# Sensor_Power_Supply.net
KiCad netlist of a schematic drawn in Altium Designer
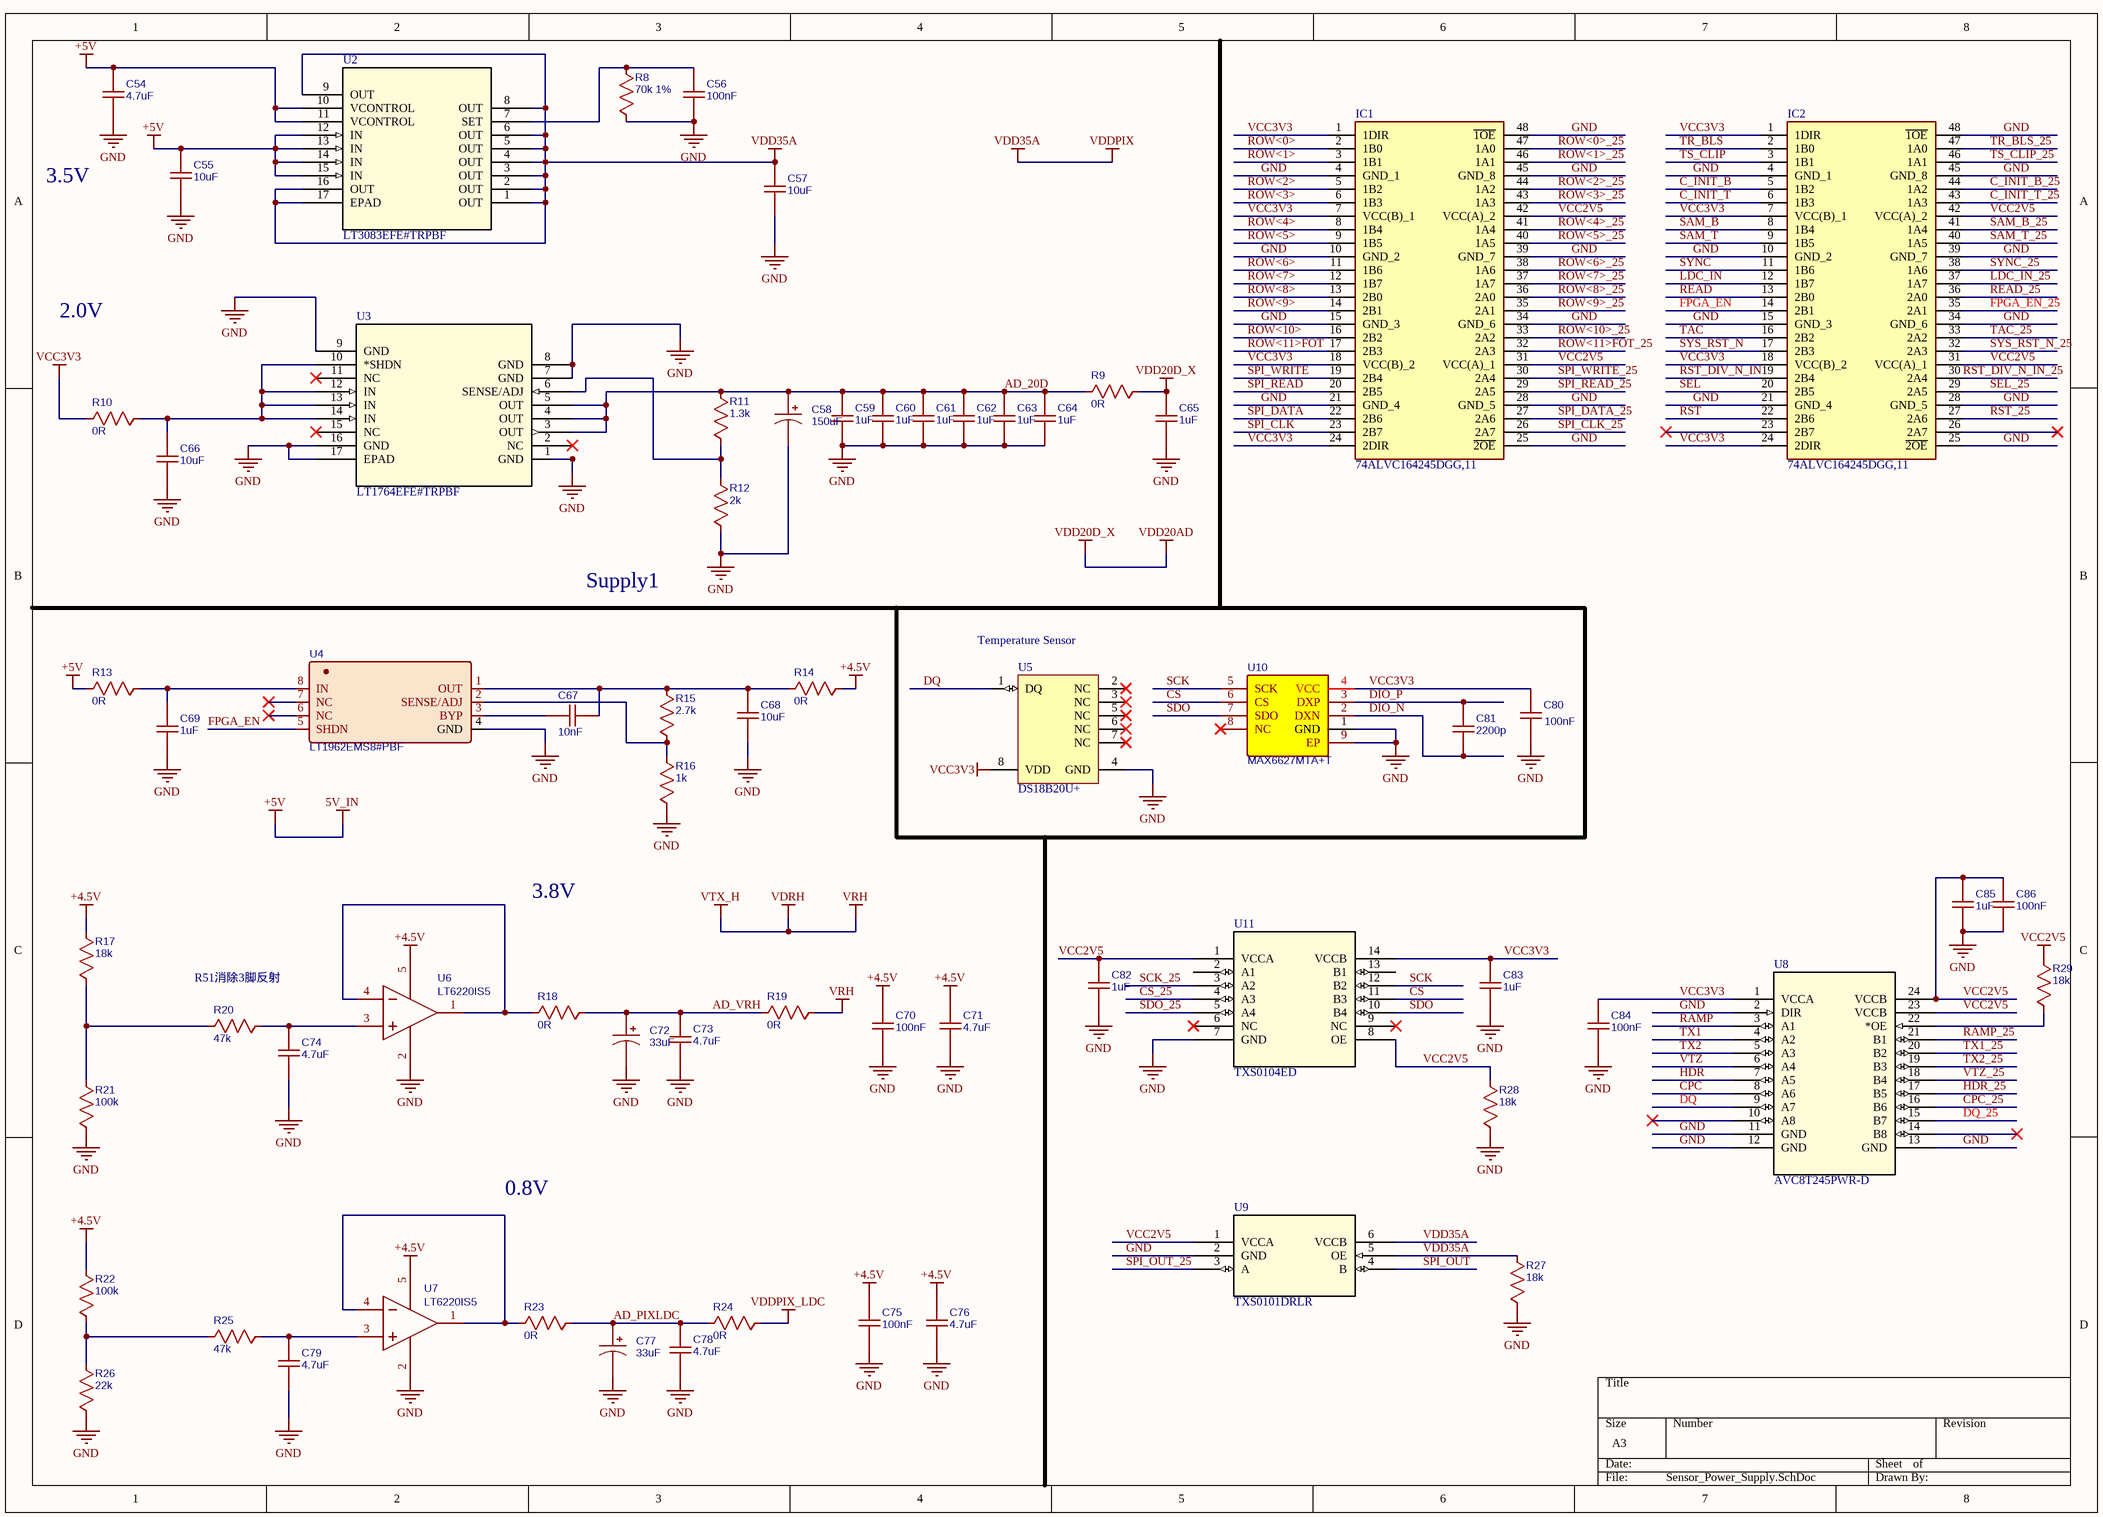
[diagram p0: Sensor_Power_Supply.SchDoc]

(export (version "E")
  (design (tool "Eeschema 10.0.6"))
  (components
    (comp (ref "C54")
      (value "4.7uF")
      (footprint "C0603")
      (fields (field (name "CONTRIBUTOR") "LCEDA_Lib"))
      (libsource (lib "Sub-board") (part "10u"))
    )
    (comp (ref "C55")
      (value "10uF")
      (footprint "C0603")
      (fields (field (name "CONTRIBUTOR") "LCEDA_Lib"))
      (libsource (lib "Sub-board") (part "10u"))
    )
    (comp (ref "C56")
      (value "100nF")
      (footprint "C0603")
      (fields (field (name "CONTRIBUTOR") "LCEDA_Lib"))
      (libsource (lib "Sub-board") (part "10u"))
    )
    (comp (ref "C57")
      (value "10uF")
      (footprint "CAP0402")
      (fields (field (name "CONTRIBUTOR") "LCEDA_Lib"))
      (libsource (lib "Sub-board") (part "10u"))
    )
    (comp (ref "C58")
      (value "150uF")
      (footprint "CASE-A_3216")
      (fields (field (name "CONTRIBUTOR") "LCEDA_Lib"))
      (libsource (lib "Sub-board") (part "150u"))
    )
    (comp (ref "C59")
      (value "1uF")
      (footprint "C0603")
      (fields (field (name "CONTRIBUTOR") "LCEDA_Lib"))
      (libsource (lib "Sub-board") (part "1u"))
    )
    (comp (ref "C60")
      (value "1uF")
      (footprint "C0603")
      (fields (field (name "CONTRIBUTOR") "LCEDA_Lib"))
      (libsource (lib "Sub-board") (part "1u"))
    )
    (comp (ref "C61")
      (value "1uF")
      (footprint "C0603")
      (fields (field (name "CONTRIBUTOR") "LCEDA_Lib"))
      (libsource (lib "Sub-board") (part "1u"))
    )
    (comp (ref "C62")
      (value "1uF")
      (footprint "C0603")
      (fields (field (name "CONTRIBUTOR") "LCEDA_Lib"))
      (libsource (lib "Sub-board") (part "1u"))
    )
    (comp (ref "C63")
      (value "1uF")
      (footprint "C0603")
      (fields (field (name "CONTRIBUTOR") "LCEDA_Lib"))
      (libsource (lib "Sub-board") (part "1u"))
    )
    (comp (ref "C64")
      (value "1uF")
      (footprint "C0603")
      (fields (field (name "CONTRIBUTOR") "LCEDA_Lib"))
      (libsource (lib "Sub-board") (part "1u"))
    )
    (comp (ref "C65")
      (value "1uF")
      (footprint "C0603")
      (fields (field (name "CONTRIBUTOR") "LCEDA_Lib"))
      (libsource (lib "Sub-board") (part "1u"))
    )
    (comp (ref "C66")
      (value "10uF")
      (footprint "C0603")
      (fields (field (name "CONTRIBUTOR") "LCEDA_Lib"))
      (libsource (lib "Sub-board") (part "10u"))
    )
    (comp (ref "C67")
      (value "10nF")
      (footprint "CAP0402")
      (fields (field (name "CONTRIBUTOR") "LCEDA_Lib"))
      (libsource (lib "Sub-board") (part "10n"))
    )
    (comp (ref "C68")
      (value "10uF")
      (footprint "C0603")
      (fields (field (name "CONTRIBUTOR") "LCEDA_Lib"))
      (libsource (lib "Sub-board") (part "10u"))
    )
    (comp (ref "C69")
      (value "1uF")
      (footprint "C0603")
      (fields (field (name "CONTRIBUTOR") "LCEDA_Lib"))
      (libsource (lib "Sub-board") (part "1u"))
    )
    (comp (ref "C70")
      (value "100nF")
      (footprint "C0603")
      (fields (field (name "CONTRIBUTOR") "LCEDA_Lib"))
      (libsource (lib "Sub-board") (part "100n"))
    )
    (comp (ref "C71")
      (value "4.7uF")
      (footprint "C0603")
      (fields (field (name "CONTRIBUTOR") "LCEDA_Lib"))
      (libsource (lib "Sub-board") (part "4.7u"))
    )
    (comp (ref "C72")
      (value "33uF")
      (footprint "CASE-A_3216")
      (fields (field (name "CONTRIBUTOR") "LCEDA_Lib"))
      (libsource (lib "Sub-board") (part "33u"))
    )
    (comp (ref "C73")
      (value "4.7uF")
      (footprint "C0603")
      (fields (field (name "CONTRIBUTOR") "LCEDA_Lib"))
      (libsource (lib "Sub-board") (part "4.7u"))
    )
    (comp (ref "C74")
      (value "4.7uF")
      (footprint "C0603")
      (fields (field (name "CONTRIBUTOR") "LCEDA_Lib"))
      (libsource (lib "Sub-board") (part "4.7u"))
    )
    (comp (ref "C75")
      (value "100nF")
      (footprint "C0603")
      (fields (field (name "CONTRIBUTOR") "LCEDA_Lib"))
      (libsource (lib "Sub-board") (part "100n"))
    )
    (comp (ref "C76")
      (value "4.7uF")
      (footprint "C0603")
      (fields (field (name "CONTRIBUTOR") "LCEDA_Lib"))
      (libsource (lib "Sub-board") (part "4.7u"))
    )
    (comp (ref "C77")
      (value "33uF")
      (footprint "CASE-A_3216")
      (fields (field (name "CONTRIBUTOR") "LCEDA_Lib"))
      (libsource (lib "Sub-board") (part "33u"))
    )
    (comp (ref "C78")
      (value "4.7uF")
      (footprint "C0603")
      (fields (field (name "CONTRIBUTOR") "LCEDA_Lib"))
      (libsource (lib "Sub-board") (part "4.7u"))
    )
    (comp (ref "C79")
      (value "4.7uF")
      (footprint "C0603")
      (fields (field (name "CONTRIBUTOR") "LCEDA_Lib"))
      (libsource (lib "Sub-board") (part "4.7u"))
    )
    (comp (ref "C80")
      (value "100nF")
      (footprint "C0603")
      (fields (field (name "CONTRIBUTOR") "LCEDA_Lib"))
      (libsource (lib "Sub-board") (part "100n"))
    )
    (comp (ref "C81")
      (value "2200p")
      (footprint "C0603")
      (fields (field (name "CONTRIBUTOR") "LCEDA_Lib"))
      (libsource (lib "Sub-board") (part "2200p"))
    )
    (comp (ref "C82")
      (value "1uF")
      (footprint "CAP0402")
      (fields (field (name "CONTRIBUTOR") "LCEDA_Lib"))
      (libsource (lib "Sub-board") (part "1u"))
    )
    (comp (ref "C83")
      (value "1uF")
      (footprint "CAP0402")
      (fields (field (name "CONTRIBUTOR") "LCEDA_Lib"))
      (libsource (lib "Sub-board") (part "1u"))
    )
    (comp (ref "C84")
      (value "100nF")
      (footprint "CAP0402")
      (fields (field (name "CONTRIBUTOR") "LCEDA_Lib"))
      (libsource (lib "Sub-board") (part "1u"))
    )
    (comp (ref "C85")
      (value "1uF")
      (footprint "CAP0402")
      (fields (field (name "CONTRIBUTOR") "LCEDA_Lib"))
      (libsource (lib "Sub-board") (part "1u"))
    )
    (comp (ref "C86")
      (value "100nF")
      (footprint "CAP0402")
      (fields (field (name "CONTRIBUTOR") "LCEDA_Lib"))
      (libsource (lib "Sub-board") (part "1u"))
    )
    (comp (ref "IC1")
      (value "74ALVC164245DGG,11")
      (footprint "SamacSys:SOP50P810X120-48N")
      (description "Integrated Circuit")
      (fields (field (name "MOUSER PART NUMBER") "771-74ALVC16424"))
      (libsource (lib "*") (part "74ALVC164245DGG,11"))
    )
    (comp (ref "IC2")
      (value "74ALVC164245DGG,11")
      (footprint "SamacSys:SOP50P810X120-48N")
      (description "Integrated Circuit")
      (fields (field (name "MOUSER PART NUMBER") "771-74ALVC16424"))
      (libsource (lib "*") (part "74ALVC164245DGG,11"))
    )
    (comp (ref "R8")
      (value "70k 1%")
      (footprint "R0603")
      (fields (field (name "CONTRIBUTOR") "LCEDA_Lib"))
      (libsource (lib "Sub-board") (part "0R"))
    )
    (comp (ref "R9")
      (value "0R")
      (footprint "R0603")
      (fields (field (name "CONTRIBUTOR") "LCEDA_Lib"))
      (libsource (lib "Sub-board") (part "0R"))
    )
    (comp (ref "R10")
      (value "0R")
      (footprint "R0603")
      (fields (field (name "CONTRIBUTOR") "LCEDA_Lib"))
      (libsource (lib "Sub-board") (part "0R"))
    )
    (comp (ref "R11")
      (value "1.3k")
      (footprint "R0603")
      (fields (field (name "CONTRIBUTOR") "LCEDA_Lib"))
      (libsource (lib "Sub-board") (part "1k"))
    )
    (comp (ref "R12")
      (value "2k")
      (footprint "R0603")
      (fields (field (name "CONTRIBUTOR") "LCEDA_Lib"))
      (libsource (lib "Sub-board") (part "1k"))
    )
    (comp (ref "R13")
      (value "0R")
      (footprint "R0603")
      (fields (field (name "CONTRIBUTOR") "LCEDA_Lib"))
      (libsource (lib "Sub-board") (part "0R"))
    )
    (comp (ref "R14")
      (value "0R")
      (footprint "R0603")
      (fields (field (name "CONTRIBUTOR") "LCEDA_Lib"))
      (libsource (lib "Sub-board") (part "0R"))
    )
    (comp (ref "R15")
      (value "2.7k")
      (footprint "RES0402")
      (fields (field (name "CONTRIBUTOR") "LCEDA_Lib"))
      (libsource (lib "Sub-board") (part "1k"))
    )
    (comp (ref "R16")
      (value "1k")
      (footprint "RES0402")
      (fields (field (name "CONTRIBUTOR") "LCEDA_Lib"))
      (libsource (lib "Sub-board") (part "2.7k"))
    )
    (comp (ref "R17")
      (value "18k")
      (footprint "R0603")
      (fields (field (name "CONTRIBUTOR") "LCEDA_Lib"))
      (libsource (lib "Sub-board") (part "22k"))
    )
    (comp (ref "R18")
      (value "0R")
      (footprint "RES0402")
      (fields (field (name "CONTRIBUTOR") "LCEDA_Lib"))
      (libsource (lib "Sub-board") (part "0R"))
    )
    (comp (ref "R19")
      (value "0R")
      (footprint "R0603")
      (fields (field (name "CONTRIBUTOR") "LCEDA_Lib"))
      (libsource (lib "Sub-board") (part "0R"))
    )
    (comp (ref "R20")
      (value "47k")
      (footprint "R0603")
      (fields (field (name "CONTRIBUTOR") "LCEDA_Lib"))
      (libsource (lib "Sub-board") (part "47k"))
    )
    (comp (ref "R21")
      (value "100k")
      (footprint "R0603")
      (fields (field (name "CONTRIBUTOR") "LCEDA_Lib"))
      (libsource (lib "Sub-board") (part "100k"))
    )
    (comp (ref "R22")
      (value "100k")
      (footprint "R0603")
      (fields (field (name "CONTRIBUTOR") "LCEDA_Lib"))
      (libsource (lib "Sub-board") (part "47k"))
    )
    (comp (ref "R23")
      (value "0R")
      (footprint "RES0402")
      (fields (field (name "CONTRIBUTOR") "LCEDA_Lib"))
      (libsource (lib "Sub-board") (part "0R"))
    )
    (comp (ref "R24")
      (value "0R")
      (footprint "R0603")
      (fields (field (name "CONTRIBUTOR") "LCEDA_Lib"))
      (libsource (lib "Sub-board") (part "0R"))
    )
    (comp (ref "R25")
      (value "47k")
      (footprint "R0603")
      (fields (field (name "CONTRIBUTOR") "LCEDA_Lib"))
      (libsource (lib "Sub-board") (part "47k"))
    )
    (comp (ref "R26")
      (value "22k")
      (footprint "R0603")
      (fields (field (name "CONTRIBUTOR") "LCEDA_Lib"))
      (libsource (lib "Sub-board") (part "47k"))
    )
    (comp (ref "R27")
      (value "18k")
      (footprint "RES0402")
      (fields (field (name "CONTRIBUTOR") "LCEDA_Lib"))
      (libsource (lib "Sub-board") (part "18k"))
    )
    (comp (ref "R28")
      (value "18k")
      (footprint "R0603")
      (fields (field (name "CONTRIBUTOR") "LCEDA_Lib"))
      (libsource (lib "Sub-board") (part "18k"))
    )
    (comp (ref "R29")
      (value "18k")
      (footprint "RES0402")
      (fields (field (name "CONTRIBUTOR") "LCEDA_Lib"))
      (libsource (lib "Sub-board") (part "18k"))
    )
    (comp (ref "U2")
      (value "LT3083EFE#TRPBF")
      (footprint "TSSOP-16_FE/BB")
      (description "LDO for 3V5")
      (fields
        (field (name "MANUFACTURER_PART_NUMBER") "lt3083efe#trpbf")
        (field (name "COPYRIGHT") "Copyright (C) 2018 Accelerated Designs. All rights reserved")
      )
      (libsource (lib "Sub-board") (part "LT3083EFE#TRPBF"))
    )
    (comp (ref "U3")
      (value "LT1764EFE#TRPBF")
      (footprint "TSSOP-16_FE/BB")
      (description "LDO for 2V")
      (fields
        (field (name "MANUFACTURER_PART_NUMBER") "lt1764efe#trpbf")
        (field (name "COPYRIGHT") "Copyright (C) 2018 Accelerated Designs. All rights reserved")
      )
      (libsource (lib "Sub-board") (part "LT1764EFE#TRPBF"))
    )
    (comp (ref "U4")
      (value "LT1962EMS8#PBF")
      (footprint "MSOP-8_L3.0-W3.0-P0.65-LS5.0-TL")
      (fields (field (name "BOM_SUPPLIER PART") "C136801") (field (name "CONTRIBUTOR") "LCSC"))
      (libsource (lib "Sub-board") (part "LT1962EMS8#PBF"))
    )
    (comp (ref "U5")
      (value "DS18B20U+")
      (footprint "MAXM-U8+1_N")
      (description "High-Precision 1-Wire Digital Thermometer, -55 to 125 degC, 8-Pin SOP (U8+1), Pb-Free")
      (fields (field (name "GENERIC PART NUMBER") "DS18B20"))
      (libsource (lib "Sub-board") (part "DS18B20U+"))
    )
    (comp (ref "U6")
      (value "LT6220IS5")
      (footprint "SOT23-5")
      (libsource (lib "Sub-board") (part "LT6220IS5"))
    )
    (comp (ref "U7")
      (value "LT6220IS5")
      (footprint "SOT23-5")
      (libsource (lib "Sub-board") (part "LT6220IS5"))
    )
    (comp (ref "U8")
      (value "AVC8T245PWR-D")
      (footprint "PW24")
      (description "8-Bit Dual-Supply Bus Transceiver with Configurable Voltage Translation and 3-State Outputs")
      (fields
        (field (name "MANUFACTURER") "Texas Instruments")
        (field (name "GENERIC_PART_NUMBER") "SN74AVC8T245")
        (field (name "COPYRIGHT") "Copyright (C) 2018 Accelerated Designs. All rights reserved")
      )
      (libsource (lib "Sub-board") (part "AVC8T245PWR-D"))
    )
    (comp (ref "U9")
      (value "TXS0101DRLR")
      (footprint "DRL6")
      (description "1-Bit Bidirectional Voltage-Level Translator for Open-Drain Application")
      (fields
        (field (name "GENERIC_PART_NUMBER") "TXS0101")
        (field (name "MANUFACTURER") "Texas Instruments")
        (field (name "COPYRIGHT") "Copyright (C) 2018 Accelerated Designs. All rights reserved")
      )
      (libsource (lib "Sub-board") (part "TXS0101DRLR"))
    )
    (comp (ref "U10")
      (value "MAX6627MTA+T")
      (footprint "MAXM-T833+2_V")
      (libsource (lib "Sub-board") (part "MAX6627MTA+T"))
    )
    (comp (ref "U11")
      (value "TXS0104ED")
      (footprint "D14")
      (description "4-Bit Bidirectional Voltage-Level Translator for Open-Drain Applications")
      (fields
        (field (name "GENERIC_PART_NUMBER") "TXS0104E")
        (field (name "MANUFACTURER") "Texas Instruments")
        (field (name "COPYRIGHT") "Copyright (C) 2018 Accelerated Designs. All rights reserved")
      )
      (libsource (lib "Sub-board") (part "TXS0104ED"))
    )
  )
  (nets
    (net (code "1") (name "+4.5V") (class "Default")
      (node (ref "C70") (pin "2") (pinfunction "2_2") (pintype "passive"))
      (node (ref "C71") (pin "2") (pinfunction "2_2") (pintype "passive"))
      (node (ref "C75") (pin "2") (pinfunction "2_2") (pintype "passive"))
      (node (ref "C76") (pin "2") (pinfunction "2_2") (pintype "passive"))
      (node (ref "R14") (pin "2") (pinfunction "2_2") (pintype "passive"))
      (node (ref "R17") (pin "2") (pinfunction "2_2") (pintype "passive"))
      (node (ref "R22") (pin "2") (pinfunction "2_2") (pintype "passive"))
      (node (ref "U6") (pin "5") (pinfunction "VS+_5") (pintype "passive"))
      (node (ref "U7") (pin "5") (pinfunction "VS+_5") (pintype "passive"))
    )
    (net (code "2") (name "+5V") (class "Default")
      (node (ref "C54") (pin "2") (pinfunction "2_2") (pintype "passive"))
      (node (ref "C55") (pin "2") (pinfunction "2_2") (pintype "passive"))
      (node (ref "R13") (pin "1") (pinfunction "1_1") (pintype "passive"))
      (node (ref "U2") (pin "10") (pinfunction "VCONTROL_10") (pintype "passive"))
      (node (ref "U2") (pin "11") (pinfunction "VCONTROL_11") (pintype "passive"))
      (node (ref "U2") (pin "12") (pinfunction "IN_12") (pintype "input"))
      (node (ref "U2") (pin "13") (pinfunction "IN_13") (pintype "input"))
      (node (ref "U2") (pin "14") (pinfunction "IN_14") (pintype "input"))
      (node (ref "U2") (pin "15") (pinfunction "IN_15") (pintype "input"))
    )
    (net (code "3") (name "/AD_20D") (class "Default")
      (node (ref "C58") (pin "1") (pinfunction "1_1") (pintype "passive"))
      (node (ref "C59") (pin "2") (pinfunction "2_2") (pintype "passive"))
      (node (ref "C60") (pin "2") (pinfunction "2_2") (pintype "passive"))
      (node (ref "C61") (pin "2") (pinfunction "2_2") (pintype "passive"))
      (node (ref "C62") (pin "2") (pinfunction "2_2") (pintype "passive"))
      (node (ref "C63") (pin "2") (pinfunction "2_2") (pintype "passive"))
      (node (ref "C64") (pin "2") (pinfunction "2_2") (pintype "passive"))
      (node (ref "R11") (pin "2") (pinfunction "2_2") (pintype "passive"))
      (node (ref "R9") (pin "1") (pinfunction "1_1") (pintype "passive"))
      (node (ref "U3") (pin "3") (pinfunction "OUT_3") (pintype "output"))
      (node (ref "U3") (pin "4") (pinfunction "OUT_4") (pintype "passive"))
      (node (ref "U3") (pin "5") (pinfunction "OUT_5") (pintype "passive"))
    )
    (net (code "4") (name "/AD_PIXLDC") (class "Default")
      (node (ref "C77") (pin "1") (pinfunction "1_1") (pintype "passive"))
      (node (ref "C78") (pin "2") (pinfunction "2_2") (pintype "passive"))
      (node (ref "R23") (pin "2") (pinfunction "2_2") (pintype "passive"))
      (node (ref "R24") (pin "1") (pinfunction "1_1") (pintype "passive"))
    )
    (net (code "5") (name "/AD_VRH") (class "Default")
      (node (ref "C72") (pin "1") (pinfunction "1_1") (pintype "passive"))
      (node (ref "C73") (pin "2") (pinfunction "2_2") (pintype "passive"))
      (node (ref "R18") (pin "2") (pinfunction "2_2") (pintype "passive"))
      (node (ref "R19") (pin "1") (pinfunction "1_1") (pintype "passive"))
    )
    (net (code "6") (name "/CPC") (class "Default")
      (node (ref "U8") (pin "8") (pinfunction "A6_8") (pintype "bidirectional"))
    )
    (net (code "7") (name "/CPC_25") (class "Default")
      (node (ref "U8") (pin "16") (pinfunction "B6_16") (pintype "bidirectional"))
    )
    (net (code "8") (name "/CS") (class "Default")
      (node (ref "U10") (pin "6") (pinfunction "CS_6") (pintype "passive"))
      (node (ref "U11") (pin "11") (pinfunction "B3_11") (pintype "bidirectional"))
    )
    (net (code "9") (name "/CS_25") (class "Default")
      (node (ref "U11") (pin "4") (pinfunction "A3_4") (pintype "bidirectional"))
    )
    (net (code "10") (name "/C_INIT_B") (class "Default")
      (node (ref "IC2") (pin "5") (pinfunction "1B2_5") (pintype "passive"))
    )
    (net (code "11") (name "/C_INIT_B_25") (class "Default")
      (node (ref "IC2") (pin "44") (pinfunction "1A2_44") (pintype "passive"))
    )
    (net (code "12") (name "/C_INIT_T") (class "Default")
      (node (ref "IC2") (pin "6") (pinfunction "1B3_6") (pintype "passive"))
    )
    (net (code "13") (name "/C_INIT_T_25") (class "Default")
      (node (ref "IC2") (pin "43") (pinfunction "1A3_43") (pintype "passive"))
    )
    (net (code "14") (name "/DIO_N") (class "Default")
      (node (ref "C81") (pin "1") (pinfunction "1_1") (pintype "passive"))
      (node (ref "U10") (pin "2") (pinfunction "DXN_2") (pintype "passive"))
    )
    (net (code "15") (name "/DIO_P") (class "Default")
      (node (ref "C81") (pin "2") (pinfunction "2_2") (pintype "passive"))
      (node (ref "U10") (pin "3") (pinfunction "DXP_3") (pintype "passive"))
    )
    (net (code "16") (name "/DQ") (class "Default")
      (node (ref "U5") (pin "1") (pinfunction "DQ_1") (pintype "bidirectional"))
      (node (ref "U8") (pin "9") (pinfunction "A7_9") (pintype "bidirectional"))
    )
    (net (code "17") (name "/DQ_25") (class "Default")
      (node (ref "U8") (pin "15") (pinfunction "B7_15") (pintype "bidirectional"))
    )
    (net (code "18") (name "/FPGA_EN") (class "Default")
      (node (ref "IC2") (pin "14") (pinfunction "2B1_14") (pintype "passive"))
      (node (ref "U4") (pin "5") (pinfunction "SHDN_5") (pintype "passive"))
    )
    (net (code "19") (name "/FPGA_EN_25") (class "Default")
      (node (ref "IC2") (pin "35") (pinfunction "2A1_35") (pintype "passive"))
    )
    (net (code "20") (name "/HDR") (class "Default")
      (node (ref "U8") (pin "7") (pinfunction "A5_7") (pintype "bidirectional"))
    )
    (net (code "21") (name "/HDR_25") (class "Default")
      (node (ref "U8") (pin "17") (pinfunction "B5_17") (pintype "bidirectional"))
    )
    (net (code "22") (name "/LDC_IN") (class "Default")
      (node (ref "IC2") (pin "12") (pinfunction "1B7_12") (pintype "passive"))
    )
    (net (code "23") (name "/LDC_IN_25") (class "Default")
      (node (ref "IC2") (pin "37") (pinfunction "1A7_37") (pintype "passive"))
    )
    (net (code "24") (name "/RAMP") (class "Default")
      (node (ref "U8") (pin "3") (pinfunction "A1_3") (pintype "bidirectional"))
    )
    (net (code "25") (name "/RAMP_25") (class "Default")
      (node (ref "U8") (pin "21") (pinfunction "B1_21") (pintype "bidirectional"))
    )
    (net (code "26") (name "/READ") (class "Default")
      (node (ref "IC2") (pin "13") (pinfunction "2B0_13") (pintype "passive"))
    )
    (net (code "27") (name "/READ_25") (class "Default")
      (node (ref "IC2") (pin "36") (pinfunction "2A0_36") (pintype "passive"))
    )
    (net (code "28") (name "/ROW<0>") (class "Default")
      (node (ref "IC1") (pin "2") (pinfunction "1B0_2") (pintype "passive"))
    )
    (net (code "29") (name "/ROW<0>_25") (class "Default")
      (node (ref "IC1") (pin "47") (pinfunction "1A0_47") (pintype "passive"))
    )
    (net (code "30") (name "/ROW<1>") (class "Default")
      (node (ref "IC1") (pin "3") (pinfunction "1B1_3") (pintype "passive"))
    )
    (net (code "31") (name "/ROW<1>_25") (class "Default")
      (node (ref "IC1") (pin "46") (pinfunction "1A1_46") (pintype "passive"))
    )
    (net (code "32") (name "/ROW<2>") (class "Default")
      (node (ref "IC1") (pin "5") (pinfunction "1B2_5") (pintype "passive"))
    )
    (net (code "33") (name "/ROW<2>_25") (class "Default")
      (node (ref "IC1") (pin "44") (pinfunction "1A2_44") (pintype "passive"))
    )
    (net (code "34") (name "/ROW<3>") (class "Default")
      (node (ref "IC1") (pin "6") (pinfunction "1B3_6") (pintype "passive"))
    )
    (net (code "35") (name "/ROW<3>_25") (class "Default")
      (node (ref "IC1") (pin "43") (pinfunction "1A3_43") (pintype "passive"))
    )
    (net (code "36") (name "/ROW<4>") (class "Default")
      (node (ref "IC1") (pin "8") (pinfunction "1B4_8") (pintype "passive"))
    )
    (net (code "37") (name "/ROW<4>_25") (class "Default")
      (node (ref "IC1") (pin "41") (pinfunction "1A4_41") (pintype "passive"))
    )
    (net (code "38") (name "/ROW<5>") (class "Default")
      (node (ref "IC1") (pin "9") (pinfunction "1B5_9") (pintype "passive"))
    )
    (net (code "39") (name "/ROW<5>_25") (class "Default")
      (node (ref "IC1") (pin "40") (pinfunction "1A5_40") (pintype "passive"))
    )
    (net (code "40") (name "/ROW<6>") (class "Default")
      (node (ref "IC1") (pin "11") (pinfunction "1B6_11") (pintype "passive"))
    )
    (net (code "41") (name "/ROW<6>_25") (class "Default")
      (node (ref "IC1") (pin "38") (pinfunction "1A6_38") (pintype "passive"))
    )
    (net (code "42") (name "/ROW<7>") (class "Default")
      (node (ref "IC1") (pin "12") (pinfunction "1B7_12") (pintype "passive"))
    )
    (net (code "43") (name "/ROW<7>_25") (class "Default")
      (node (ref "IC1") (pin "37") (pinfunction "1A7_37") (pintype "passive"))
    )
    (net (code "44") (name "/ROW<8>") (class "Default")
      (node (ref "IC1") (pin "13") (pinfunction "2B0_13") (pintype "passive"))
    )
    (net (code "45") (name "/ROW<8>_25") (class "Default")
      (node (ref "IC1") (pin "36") (pinfunction "2A0_36") (pintype "passive"))
    )
    (net (code "46") (name "/ROW<9>") (class "Default")
      (node (ref "IC1") (pin "14") (pinfunction "2B1_14") (pintype "passive"))
    )
    (net (code "47") (name "/ROW<9>_25") (class "Default")
      (node (ref "IC1") (pin "35") (pinfunction "2A1_35") (pintype "passive"))
    )
    (net (code "48") (name "/ROW<10>") (class "Default")
      (node (ref "IC1") (pin "16") (pinfunction "2B2_16") (pintype "passive"))
    )
    (net (code "49") (name "/ROW<10>_25") (class "Default")
      (node (ref "IC1") (pin "33") (pinfunction "2A2_33") (pintype "passive"))
    )
    (net (code "50") (name "/ROW<11>FOT") (class "Default")
      (node (ref "IC1") (pin "17") (pinfunction "2B3_17") (pintype "passive"))
    )
    (net (code "51") (name "/ROW<11>FOT_25") (class "Default")
      (node (ref "IC1") (pin "32") (pinfunction "2A3_32") (pintype "passive"))
    )
    (net (code "52") (name "/RST") (class "Default")
      (node (ref "IC2") (pin "22") (pinfunction "2B6_22") (pintype "passive"))
    )
    (net (code "53") (name "/RST_25") (class "Default")
      (node (ref "IC2") (pin "27") (pinfunction "2A6_27") (pintype "passive"))
    )
    (net (code "54") (name "/RST_DIV_N_IN") (class "Default")
      (node (ref "IC2") (pin "19") (pinfunction "2B4_19") (pintype "passive"))
    )
    (net (code "55") (name "/RST_DIV_N_IN_25") (class "Default")
      (node (ref "IC2") (pin "30") (pinfunction "2A4_30") (pintype "passive"))
    )
    (net (code "56") (name "/SAM_B") (class "Default")
      (node (ref "IC2") (pin "8") (pinfunction "1B4_8") (pintype "passive"))
    )
    (net (code "57") (name "/SAM_B_25") (class "Default")
      (node (ref "IC2") (pin "41") (pinfunction "1A4_41") (pintype "passive"))
    )
    (net (code "58") (name "/SAM_T") (class "Default")
      (node (ref "IC2") (pin "9") (pinfunction "1B5_9") (pintype "passive"))
    )
    (net (code "59") (name "/SAM_T_25") (class "Default")
      (node (ref "IC2") (pin "40") (pinfunction "1A5_40") (pintype "passive"))
    )
    (net (code "60") (name "/SCK") (class "Default")
      (node (ref "U10") (pin "5") (pinfunction "SCK_5") (pintype "passive"))
      (node (ref "U11") (pin "12") (pinfunction "B2_12") (pintype "bidirectional"))
    )
    (net (code "61") (name "/SCK_25") (class "Default")
      (node (ref "U11") (pin "3") (pinfunction "A2_3") (pintype "bidirectional"))
    )
    (net (code "62") (name "/SDO") (class "Default")
      (node (ref "U10") (pin "7") (pinfunction "SDO_7") (pintype "passive"))
      (node (ref "U11") (pin "10") (pinfunction "B4_10") (pintype "bidirectional"))
    )
    (net (code "63") (name "/SDO_25") (class "Default")
      (node (ref "U11") (pin "5") (pinfunction "A4_5") (pintype "bidirectional"))
    )
    (net (code "64") (name "/SEL") (class "Default")
      (node (ref "IC2") (pin "20") (pinfunction "2B5_20") (pintype "passive"))
    )
    (net (code "65") (name "/SEL_25") (class "Default")
      (node (ref "IC2") (pin "29") (pinfunction "2A5_29") (pintype "passive"))
    )
    (net (code "66") (name "/SPI_CLK") (class "Default")
      (node (ref "IC1") (pin "23") (pinfunction "2B7_23") (pintype "passive"))
    )
    (net (code "67") (name "/SPI_CLK_25") (class "Default")
      (node (ref "IC1") (pin "26") (pinfunction "2A7_26") (pintype "passive"))
    )
    (net (code "68") (name "/SPI_DATA") (class "Default")
      (node (ref "IC1") (pin "22") (pinfunction "2B6_22") (pintype "passive"))
    )
    (net (code "69") (name "/SPI_DATA_25") (class "Default")
      (node (ref "IC1") (pin "27") (pinfunction "2A6_27") (pintype "passive"))
    )
    (net (code "70") (name "/SPI_OUT") (class "Default")
      (node (ref "U9") (pin "4") (pinfunction "B_4") (pintype "bidirectional"))
    )
    (net (code "71") (name "/SPI_OUT_25") (class "Default")
      (node (ref "U9") (pin "3") (pinfunction "A_3") (pintype "bidirectional"))
    )
    (net (code "72") (name "/SPI_READ") (class "Default")
      (node (ref "IC1") (pin "20") (pinfunction "2B5_20") (pintype "passive"))
    )
    (net (code "73") (name "/SPI_READ_25") (class "Default")
      (node (ref "IC1") (pin "29") (pinfunction "2A5_29") (pintype "passive"))
    )
    (net (code "74") (name "/SPI_WRITE") (class "Default")
      (node (ref "IC1") (pin "19") (pinfunction "2B4_19") (pintype "passive"))
    )
    (net (code "75") (name "/SPI_WRITE_25") (class "Default")
      (node (ref "IC1") (pin "30") (pinfunction "2A4_30") (pintype "passive"))
    )
    (net (code "76") (name "/SYNC") (class "Default")
      (node (ref "IC2") (pin "11") (pinfunction "1B6_11") (pintype "passive"))
    )
    (net (code "77") (name "/SYNC_25") (class "Default")
      (node (ref "IC2") (pin "38") (pinfunction "1A6_38") (pintype "passive"))
    )
    (net (code "78") (name "/SYS_RST_N") (class "Default")
      (node (ref "IC2") (pin "17") (pinfunction "2B3_17") (pintype "passive"))
    )
    (net (code "79") (name "/SYS_RST_N_25") (class "Default")
      (node (ref "IC2") (pin "32") (pinfunction "2A3_32") (pintype "passive"))
    )
    (net (code "80") (name "/TAC") (class "Default")
      (node (ref "IC2") (pin "16") (pinfunction "2B2_16") (pintype "passive"))
    )
    (net (code "81") (name "/TAC_25") (class "Default")
      (node (ref "IC2") (pin "33") (pinfunction "2A2_33") (pintype "passive"))
    )
    (net (code "82") (name "/TR_BLS") (class "Default")
      (node (ref "IC2") (pin "2") (pinfunction "1B0_2") (pintype "passive"))
    )
    (net (code "83") (name "/TR_BLS_25") (class "Default")
      (node (ref "IC2") (pin "47") (pinfunction "1A0_47") (pintype "passive"))
    )
    (net (code "84") (name "/TS_CLIP") (class "Default")
      (node (ref "IC2") (pin "3") (pinfunction "1B1_3") (pintype "passive"))
    )
    (net (code "85") (name "/TS_CLIP_25") (class "Default")
      (node (ref "IC2") (pin "46") (pinfunction "1A1_46") (pintype "passive"))
    )
    (net (code "86") (name "/TX1") (class "Default")
      (node (ref "U8") (pin "4") (pinfunction "A2_4") (pintype "bidirectional"))
    )
    (net (code "87") (name "/TX1_25") (class "Default")
      (node (ref "U8") (pin "20") (pinfunction "B2_20") (pintype "bidirectional"))
    )
    (net (code "88") (name "/TX2") (class "Default")
      (node (ref "U8") (pin "5") (pinfunction "A3_5") (pintype "bidirectional"))
    )
    (net (code "89") (name "/TX2_25") (class "Default")
      (node (ref "U8") (pin "19") (pinfunction "B3_19") (pintype "bidirectional"))
    )
    (net (code "90") (name "/VTZ") (class "Default")
      (node (ref "U8") (pin "6") (pinfunction "A4_6") (pintype "bidirectional"))
    )
    (net (code "91") (name "/VTZ_25") (class "Default")
      (node (ref "U8") (pin "18") (pinfunction "B4_18") (pintype "bidirectional"))
    )
    (net (code "92") (name "GND") (class "Default")
      (node (ref "C54") (pin "1") (pinfunction "1_1") (pintype "passive"))
      (node (ref "C55") (pin "1") (pinfunction "1_1") (pintype "passive"))
      (node (ref "C56") (pin "1") (pinfunction "1_1") (pintype "passive"))
      (node (ref "C57") (pin "1") (pinfunction "1_1") (pintype "passive"))
      (node (ref "C58") (pin "2") (pinfunction "2_2") (pintype "passive"))
      (node (ref "C59") (pin "1") (pinfunction "1_1") (pintype "passive"))
      (node (ref "C60") (pin "1") (pinfunction "1_1") (pintype "passive"))
      (node (ref "C61") (pin "1") (pinfunction "1_1") (pintype "passive"))
      (node (ref "C62") (pin "1") (pinfunction "1_1") (pintype "passive"))
      (node (ref "C63") (pin "1") (pinfunction "1_1") (pintype "passive"))
      (node (ref "C64") (pin "1") (pinfunction "1_1") (pintype "passive"))
      (node (ref "C65") (pin "1") (pinfunction "1_1") (pintype "passive"))
      (node (ref "C66") (pin "1") (pinfunction "1_1") (pintype "passive"))
      (node (ref "C68") (pin "2") (pinfunction "2_2") (pintype "passive"))
      (node (ref "C69") (pin "1") (pinfunction "1_1") (pintype "passive"))
      (node (ref "C70") (pin "1") (pinfunction "1_1") (pintype "passive"))
      (node (ref "C71") (pin "1") (pinfunction "1_1") (pintype "passive"))
      (node (ref "C72") (pin "2") (pinfunction "2_2") (pintype "passive"))
      (node (ref "C73") (pin "1") (pinfunction "1_1") (pintype "passive"))
      (node (ref "C74") (pin "1") (pinfunction "1_1") (pintype "passive"))
      (node (ref "C75") (pin "1") (pinfunction "1_1") (pintype "passive"))
      (node (ref "C76") (pin "1") (pinfunction "1_1") (pintype "passive"))
      (node (ref "C77") (pin "2") (pinfunction "2_2") (pintype "passive"))
      (node (ref "C78") (pin "1") (pinfunction "1_1") (pintype "passive"))
      (node (ref "C79") (pin "1") (pinfunction "1_1") (pintype "passive"))
      (node (ref "C80") (pin "1") (pinfunction "1_1") (pintype "passive"))
      (node (ref "C82") (pin "1") (pinfunction "1_1") (pintype "passive"))
      (node (ref "C83") (pin "1") (pinfunction "1_1") (pintype "passive"))
      (node (ref "C84") (pin "1") (pinfunction "1_1") (pintype "passive"))
      (node (ref "C85") (pin "1") (pinfunction "1_1") (pintype "passive"))
      (node (ref "C86") (pin "1") (pinfunction "1_1") (pintype "passive"))
      (node (ref "IC1") (pin "10") (pinfunction "GND_2_10") (pintype "passive"))
      (node (ref "IC1") (pin "15") (pinfunction "GND_3_15") (pintype "passive"))
      (node (ref "IC1") (pin "21") (pinfunction "GND_4_21") (pintype "passive"))
      (node (ref "IC1") (pin "25") (pinfunction "~{2OE}_25") (pintype "passive"))
      (node (ref "IC1") (pin "28") (pinfunction "GND_5_28") (pintype "passive"))
      (node (ref "IC1") (pin "34") (pinfunction "GND_6_34") (pintype "passive"))
      (node (ref "IC1") (pin "39") (pinfunction "GND_7_39") (pintype "passive"))
      (node (ref "IC1") (pin "4") (pinfunction "GND_1_4") (pintype "passive"))
      (node (ref "IC1") (pin "45") (pinfunction "GND_8_45") (pintype "passive"))
      (node (ref "IC1") (pin "48") (pinfunction "~{1OE}_48") (pintype "passive"))
      (node (ref "IC2") (pin "10") (pinfunction "GND_2_10") (pintype "passive"))
      (node (ref "IC2") (pin "15") (pinfunction "GND_3_15") (pintype "passive"))
      (node (ref "IC2") (pin "21") (pinfunction "GND_4_21") (pintype "passive"))
      (node (ref "IC2") (pin "25") (pinfunction "~{2OE}_25") (pintype "passive"))
      (node (ref "IC2") (pin "28") (pinfunction "GND_5_28") (pintype "passive"))
      (node (ref "IC2") (pin "34") (pinfunction "GND_6_34") (pintype "passive"))
      (node (ref "IC2") (pin "39") (pinfunction "GND_7_39") (pintype "passive"))
      (node (ref "IC2") (pin "4") (pinfunction "GND_1_4") (pintype "passive"))
      (node (ref "IC2") (pin "45") (pinfunction "GND_8_45") (pintype "passive"))
      (node (ref "IC2") (pin "48") (pinfunction "~{1OE}_48") (pintype "passive"))
      (node (ref "R12") (pin "1") (pinfunction "1_1") (pintype "passive"))
      (node (ref "R16") (pin "1") (pinfunction "1_1") (pintype "passive"))
      (node (ref "R21") (pin "1") (pinfunction "1_1") (pintype "passive"))
      (node (ref "R26") (pin "1") (pinfunction "1_1") (pintype "passive"))
      (node (ref "R27") (pin "1") (pinfunction "1_1") (pintype "passive"))
      (node (ref "R28") (pin "1") (pinfunction "1_1") (pintype "passive"))
      (node (ref "R8") (pin "1") (pinfunction "1_1") (pintype "passive"))
      (node (ref "U10") (pin "1") (pinfunction "GND_1") (pintype "passive"))
      (node (ref "U10") (pin "9") (pinfunction "EP_9") (pintype "passive"))
      (node (ref "U11") (pin "7") (pinfunction "GND_7") (pintype "power_in"))
      (node (ref "U3") (pin "1") (pinfunction "GND_1") (pintype "power_in"))
      (node (ref "U3") (pin "16") (pinfunction "GND_16") (pintype "power_in"))
      (node (ref "U3") (pin "17") (pinfunction "EPAD_17") (pintype "passive"))
      (node (ref "U3") (pin "7") (pinfunction "GND_7") (pintype "power_in"))
      (node (ref "U3") (pin "8") (pinfunction "GND_8") (pintype "power_in"))
      (node (ref "U3") (pin "9") (pinfunction "GND_9") (pintype "power_in"))
      (node (ref "U4") (pin "4") (pinfunction "GND_4") (pintype "passive"))
      (node (ref "U5") (pin "4") (pinfunction "GND_4") (pintype "power_in"))
      (node (ref "U6") (pin "2") (pinfunction "VS-_2") (pintype "passive"))
      (node (ref "U7") (pin "2") (pinfunction "VS-_2") (pintype "passive"))
      (node (ref "U8") (pin "11") (pinfunction "GND_11") (pintype "power_in"))
      (node (ref "U8") (pin "12") (pinfunction "GND_12") (pintype "power_in"))
      (node (ref "U8") (pin "13") (pinfunction "GND_13") (pintype "power_in"))
      (node (ref "U8") (pin "2") (pinfunction "DIR_2") (pintype "input"))
      (node (ref "U9") (pin "2") (pinfunction "GND_2") (pintype "power_in"))
    )
    (net (code "93") (name "Net-(R17-Pad1)") (class "Default")
      (node (ref "R17") (pin "1") (pinfunction "1_1") (pintype "passive"))
      (node (ref "R20") (pin "1") (pinfunction "1_1") (pintype "passive"))
      (node (ref "R21") (pin "2") (pinfunction "2_2") (pintype "passive"))
    )
    (net (code "94") (name "Net-(R22-Pad1)") (class "Default")
      (node (ref "R22") (pin "1") (pinfunction "1_1") (pintype "passive"))
      (node (ref "R25") (pin "1") (pinfunction "1_1") (pintype "passive"))
      (node (ref "R26") (pin "2") (pinfunction "2_2") (pintype "passive"))
    )
    (net (code "95") (name "Net-(U2-SET)") (class "Default")
      (node (ref "C56") (pin "2") (pinfunction "2_2") (pintype "passive"))
      (node (ref "R8") (pin "2") (pinfunction "2_2") (pintype "passive"))
      (node (ref "U2") (pin "7") (pinfunction "SET_7") (pintype "passive"))
    )
    (net (code "96") (name "Net-(U3-*SHDN)") (class "Default")
      (node (ref "C66") (pin "2") (pinfunction "2_2") (pintype "passive"))
      (node (ref "R10") (pin "2") (pinfunction "2_2") (pintype "passive"))
      (node (ref "U3") (pin "10") (pinfunction "*SHDN_10") (pintype "passive"))
      (node (ref "U3") (pin "12") (pinfunction "IN_12") (pintype "input"))
      (node (ref "U3") (pin "13") (pinfunction "IN_13") (pintype "input"))
      (node (ref "U3") (pin "14") (pinfunction "IN_14") (pintype "input"))
    )
    (net (code "97") (name "Net-(U3-SENSE{slash}ADJ)") (class "Default")
      (node (ref "R11") (pin "1") (pinfunction "1_1") (pintype "passive"))
      (node (ref "R12") (pin "2") (pinfunction "2_2") (pintype "passive"))
      (node (ref "U3") (pin "6") (pinfunction "SENSE/ADJ_6") (pintype "input"))
    )
    (net (code "98") (name "Net-(U4-BYP)") (class "Default")
      (node (ref "C67") (pin "2") (pinfunction "2_2") (pintype "passive"))
      (node (ref "U4") (pin "3") (pinfunction "BYP_3") (pintype "passive"))
    )
    (net (code "99") (name "Net-(U4-IN)") (class "Default")
      (node (ref "C69") (pin "2") (pinfunction "2_2") (pintype "passive"))
      (node (ref "R13") (pin "2") (pinfunction "2_2") (pintype "passive"))
      (node (ref "U4") (pin "8") (pinfunction "IN_8") (pintype "passive"))
    )
    (net (code "100") (name "Net-(U4-OUT)") (class "Default")
      (node (ref "C67") (pin "1") (pinfunction "1_1") (pintype "passive"))
      (node (ref "C68") (pin "1") (pinfunction "1_1") (pintype "passive"))
      (node (ref "R14") (pin "1") (pinfunction "1_1") (pintype "passive"))
      (node (ref "R15") (pin "2") (pinfunction "2_2") (pintype "passive"))
      (node (ref "U4") (pin "1") (pinfunction "OUT_1") (pintype "passive"))
    )
    (net (code "101") (name "Net-(U4-SENSE{slash}ADJ)") (class "Default")
      (node (ref "R15") (pin "1") (pinfunction "1_1") (pintype "passive"))
      (node (ref "R16") (pin "2") (pinfunction "2_2") (pintype "passive"))
      (node (ref "U4") (pin "2") (pinfunction "SENSE/ADJ_2") (pintype "passive"))
    )
    (net (code "102") (name "Net-(U6-+IN)") (class "Default")
      (node (ref "C74") (pin "2") (pinfunction "2_2") (pintype "passive"))
      (node (ref "R20") (pin "2") (pinfunction "2_2") (pintype "passive"))
      (node (ref "U6") (pin "3") (pinfunction "+IN_3") (pintype "passive"))
    )
    (net (code "103") (name "Net-(U6--IN)") (class "Default")
      (node (ref "R18") (pin "1") (pinfunction "1_1") (pintype "passive"))
      (node (ref "U6") (pin "1") (pinfunction "VOUT_1") (pintype "passive"))
      (node (ref "U6") (pin "4") (pinfunction "-IN_4") (pintype "passive"))
    )
    (net (code "104") (name "Net-(U7-+IN)") (class "Default")
      (node (ref "C79") (pin "2") (pinfunction "2_2") (pintype "passive"))
      (node (ref "R25") (pin "2") (pinfunction "2_2") (pintype "passive"))
      (node (ref "U7") (pin "3") (pinfunction "+IN_3") (pintype "passive"))
    )
    (net (code "105") (name "Net-(U7--IN)") (class "Default")
      (node (ref "R23") (pin "1") (pinfunction "1_1") (pintype "passive"))
      (node (ref "U7") (pin "1") (pinfunction "VOUT_1") (pintype "passive"))
      (node (ref "U7") (pin "4") (pinfunction "-IN_4") (pintype "passive"))
    )
    (net (code "106") (name "Net-(U8-*OE)") (class "Default")
      (node (ref "R29") (pin "1") (pinfunction "1_1") (pintype "passive"))
      (node (ref "U8") (pin "22") (pinfunction "*OE_22") (pintype "input"))
    )
    (net (code "107") (name "VCC2V5") (class "Default")
      (node (ref "C82") (pin "2") (pinfunction "2_2") (pintype "passive"))
      (node (ref "C85") (pin "2") (pinfunction "2_2") (pintype "passive"))
      (node (ref "C86") (pin "2") (pinfunction "2_2") (pintype "passive"))
      (node (ref "IC1") (pin "31") (pinfunction "VCC(A)_1_31") (pintype "passive"))
      (node (ref "IC1") (pin "42") (pinfunction "VCC(A)_2_42") (pintype "passive"))
      (node (ref "IC2") (pin "31") (pinfunction "VCC(A)_1_31") (pintype "passive"))
      (node (ref "IC2") (pin "42") (pinfunction "VCC(A)_2_42") (pintype "passive"))
      (node (ref "R28") (pin "2") (pinfunction "2_2") (pintype "passive"))
      (node (ref "R29") (pin "2") (pinfunction "2_2") (pintype "passive"))
      (node (ref "U11") (pin "1") (pinfunction "VCCA_1") (pintype "power_in"))
      (node (ref "U11") (pin "8") (pinfunction "OE_8") (pintype "passive"))
      (node (ref "U8") (pin "23") (pinfunction "VCCB_23") (pintype "power_in"))
      (node (ref "U8") (pin "24") (pinfunction "VCCB_24") (pintype "power_in"))
      (node (ref "U9") (pin "1") (pinfunction "VCCA_1") (pintype "power_in"))
    )
    (net (code "108") (name "VCC3V3") (class "Default")
      (node (ref "C80") (pin "2") (pinfunction "2_2") (pintype "passive"))
      (node (ref "C83") (pin "2") (pinfunction "2_2") (pintype "passive"))
      (node (ref "C84") (pin "2") (pinfunction "2_2") (pintype "passive"))
      (node (ref "IC1") (pin "1") (pinfunction "1DIR_1") (pintype "passive"))
      (node (ref "IC1") (pin "18") (pinfunction "VCC(B)_2_18") (pintype "passive"))
      (node (ref "IC1") (pin "24") (pinfunction "2DIR_24") (pintype "passive"))
      (node (ref "IC1") (pin "7") (pinfunction "VCC(B)_1_7") (pintype "passive"))
      (node (ref "IC2") (pin "1") (pinfunction "1DIR_1") (pintype "passive"))
      (node (ref "IC2") (pin "18") (pinfunction "VCC(B)_2_18") (pintype "passive"))
      (node (ref "IC2") (pin "24") (pinfunction "2DIR_24") (pintype "passive"))
      (node (ref "IC2") (pin "7") (pinfunction "VCC(B)_1_7") (pintype "passive"))
      (node (ref "R10") (pin "1") (pinfunction "1_1") (pintype "passive"))
      (node (ref "U10") (pin "4") (pinfunction "VCC_4") (pintype "passive"))
      (node (ref "U11") (pin "14") (pinfunction "VCCB_14") (pintype "power_in"))
      (node (ref "U5") (pin "8") (pinfunction "VDD_8") (pintype "power_in"))
      (node (ref "U8") (pin "1") (pinfunction "VCCA_1") (pintype "power_in"))
    )
    (net (code "109") (name "VDD20AD") (class "Default")
      (node (ref "C65") (pin "2") (pinfunction "2_2") (pintype "passive"))
      (node (ref "R9") (pin "2") (pinfunction "2_2") (pintype "passive"))
    )
    (net (code "110") (name "VDD35A") (class "Default")
      (node (ref "C57") (pin "2") (pinfunction "2_2") (pintype "passive"))
      (node (ref "R27") (pin "2") (pinfunction "2_2") (pintype "passive"))
      (node (ref "U2") (pin "1") (pinfunction "OUT_1") (pintype "passive"))
      (node (ref "U2") (pin "16") (pinfunction "OUT_16") (pintype "passive"))
      (node (ref "U2") (pin "17") (pinfunction "EPAD_17") (pintype "passive"))
      (node (ref "U2") (pin "2") (pinfunction "OUT_2") (pintype "passive"))
      (node (ref "U2") (pin "3") (pinfunction "OUT_3") (pintype "passive"))
      (node (ref "U2") (pin "4") (pinfunction "OUT_4") (pintype "passive"))
      (node (ref "U2") (pin "5") (pinfunction "OUT_5") (pintype "passive"))
      (node (ref "U2") (pin "6") (pinfunction "OUT_6") (pintype "passive"))
      (node (ref "U2") (pin "8") (pinfunction "OUT_8") (pintype "passive"))
      (node (ref "U2") (pin "9") (pinfunction "OUT_9") (pintype "passive"))
      (node (ref "U9") (pin "5") (pinfunction "OE_5") (pintype "input"))
      (node (ref "U9") (pin "6") (pinfunction "VCCB_6") (pintype "power_in"))
    )
    (net (code "111") (name "VDDPIX_LDC") (class "Default")
      (node (ref "R24") (pin "2") (pinfunction "2_2") (pintype "passive"))
    )
    (net (code "112") (name "VDRH") (class "Default")
      (node (ref "R19") (pin "2") (pinfunction "2_2") (pintype "passive"))
    )
    (net (code "113") (name "unconnected-(IC2-2A7-Pad26)") (class "Default")
      (node (ref "IC2") (pin "26") (pinfunction "2A7_26") (pintype "passive+no_connect"))
    )
    (net (code "114") (name "unconnected-(IC2-2B7-Pad23)") (class "Default")
      (node (ref "IC2") (pin "23") (pinfunction "2B7_23") (pintype "passive+no_connect"))
    )
    (net (code "115") (name "unconnected-(U3-NC-Pad2)") (class "Default")
      (node (ref "U3") (pin "2") (pinfunction "NC_2") (pintype "passive+no_connect"))
    )
    (net (code "116") (name "unconnected-(U3-NC-Pad11)") (class "Default")
      (node (ref "U3") (pin "11") (pinfunction "NC_11") (pintype "passive+no_connect"))
    )
    (net (code "117") (name "unconnected-(U3-NC-Pad15)") (class "Default")
      (node (ref "U3") (pin "15") (pinfunction "NC_15") (pintype "passive+no_connect"))
    )
    (net (code "118") (name "unconnected-(U4-NC-Pad6)") (class "Default")
      (node (ref "U4") (pin "6") (pinfunction "NC_6") (pintype "passive+no_connect"))
    )
    (net (code "119") (name "unconnected-(U4-NC-Pad7)") (class "Default")
      (node (ref "U4") (pin "7") (pinfunction "NC_7") (pintype "passive+no_connect"))
    )
    (net (code "120") (name "unconnected-(U5-NC-Pad2)") (class "Default")
      (node (ref "U5") (pin "2") (pinfunction "NC_2") (pintype "passive+no_connect"))
    )
    (net (code "121") (name "unconnected-(U5-NC-Pad3)") (class "Default")
      (node (ref "U5") (pin "3") (pinfunction "NC_3") (pintype "passive+no_connect"))
    )
    (net (code "122") (name "unconnected-(U5-NC-Pad5)") (class "Default")
      (node (ref "U5") (pin "5") (pinfunction "NC_5") (pintype "passive+no_connect"))
    )
    (net (code "123") (name "unconnected-(U5-NC-Pad6)") (class "Default")
      (node (ref "U5") (pin "6") (pinfunction "NC_6") (pintype "passive+no_connect"))
    )
    (net (code "124") (name "unconnected-(U5-NC-Pad7)") (class "Default")
      (node (ref "U5") (pin "7") (pinfunction "NC_7") (pintype "passive+no_connect"))
    )
    (net (code "125") (name "unconnected-(U8-A8-Pad10)") (class "Default")
      (node (ref "U8") (pin "10") (pinfunction "A8_10") (pintype "bidirectional+no_connect"))
    )
    (net (code "126") (name "unconnected-(U8-B8-Pad14)") (class "Default")
      (node (ref "U8") (pin "14") (pinfunction "B8_14") (pintype "bidirectional+no_connect"))
    )
    (net (code "127") (name "unconnected-(U10-NC-Pad8)") (class "Default")
      (node (ref "U10") (pin "8") (pinfunction "NC_8") (pintype "passive+no_connect"))
    )
    (net (code "128") (name "unconnected-(U11-A1-Pad2)") (class "Default")
      (node (ref "U11") (pin "2") (pinfunction "A1_2") (pintype "bidirectional"))
    )
    (net (code "129") (name "unconnected-(U11-B1-Pad13)") (class "Default")
      (node (ref "U11") (pin "13") (pinfunction "B1_13") (pintype "bidirectional"))
    )
    (net (code "130") (name "unconnected-(U11-NC-Pad6)") (class "Default")
      (node (ref "U11") (pin "6") (pinfunction "NC_6") (pintype "passive+no_connect"))
    )
    (net (code "131") (name "unconnected-(U11-NC-Pad9)") (class "Default")
      (node (ref "U11") (pin "9") (pinfunction "NC_9") (pintype "passive+no_connect"))
    )
  )
)
